# power-v12.net
KiCad netlist of a schematic drawn in Altium Designer
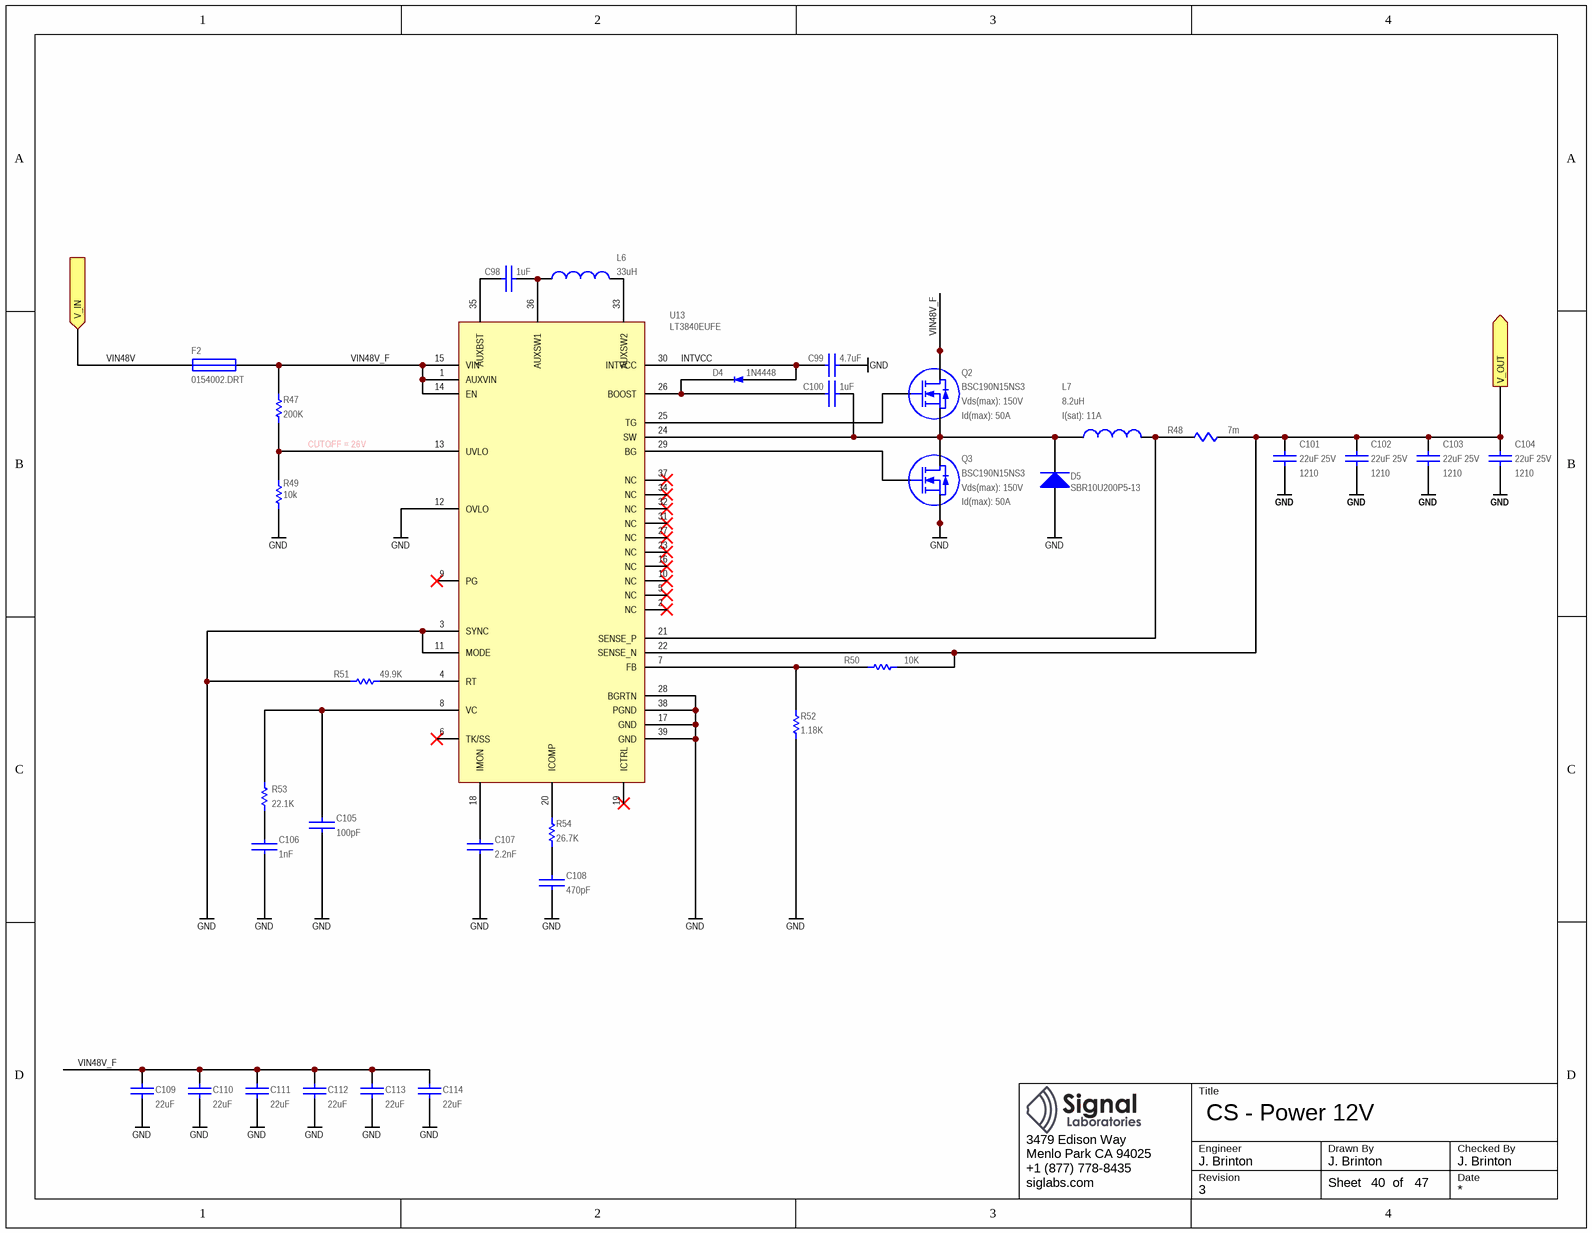
[diagram p0: power-v12.SchDoc]

(export (version "E")
  (design (tool "Eeschema 10.0.6"))
  (components
    (comp (ref "C98")
      (value "1uF")
      (footprint "CAPC100X50X55L25N")
      (description "Ceramic Capacitor 1uF ±10% 10V X5R 0402")
      (fields (field (name "MANUFACTURER") "Murata") (field (name "TOLERANCE") "±10%"))
      (libsource (lib "*") (part "CAP"))
    )
    (comp (ref "C99")
      (value "4.7uF")
      (footprint "CAPC160X80X90L20N")
      (description "Ceramic Capacitor 4.7uF ±10% 25V X5R 0603")
      (fields (field (name "VOLTAGE") "25V") (field (name "MANUFACTURER") "Murata"))
      (libsource (lib "generic") (part "CAP 0603"))
    )
    (comp (ref "C100")
      (value "1uF")
      (footprint "CAPC100X50X55L25N")
      (description "Ceramic Capacitor 1uF ±10% 10V X5R 0402")
      (fields (field (name "MANUFACTURER") "Murata") (field (name "TOLERANCE") "±10%"))
      (libsource (lib "*") (part "CAP"))
    )
    (comp (ref "C101")
      (value "22uF")
      (footprint "CAPC320X250X270L50N")
      (description "Ceramic Capacitor 22uF ±10% 25V X7R 1210")
      (fields
        (field (name "MANUFACTURER") "Murata")
        (field (name "TOLERANCE") "±10%")
        (field (name "VOLTAGE") "25V")
        (field (name "PACKAGE") "1210")
      )
      (libsource (lib "generic") (part "CAP"))
    )
    (comp (ref "C102")
      (value "22uF")
      (footprint "CAPC320X250X270L50N")
      (description "Ceramic Capacitor 22uF ±10% 25V X7R 1210")
      (fields
        (field (name "MANUFACTURER") "Murata")
        (field (name "TOLERANCE") "±10%")
        (field (name "VOLTAGE") "25V")
        (field (name "PACKAGE") "1210")
      )
      (libsource (lib "generic") (part "CAP"))
    )
    (comp (ref "C103")
      (value "22uF")
      (footprint "CAPC320X250X270L50N")
      (description "Ceramic Capacitor 22uF ±10% 25V X7R 1210")
      (fields
        (field (name "MANUFACTURER") "Murata")
        (field (name "TOLERANCE") "±10%")
        (field (name "VOLTAGE") "25V")
        (field (name "PACKAGE") "1210")
      )
      (libsource (lib "generic") (part "CAP"))
    )
    (comp (ref "C104")
      (value "22uF")
      (footprint "CAPC320X250X270L50N")
      (description "Ceramic Capacitor 22uF ±10% 25V X7R 1210")
      (fields
        (field (name "MANUFACTURER") "Murata")
        (field (name "TOLERANCE") "±10%")
        (field (name "VOLTAGE") "25V")
        (field (name "PACKAGE") "1210")
      )
      (libsource (lib "generic") (part "CAP"))
    )
    (comp (ref "C105")
      (value "100pF")
      (footprint "CAPC100X50X55L25N")
      (description "Ceramic Capacitor 100pF ±5% 50V NP0 0402")
      (fields (field (name "MANUFACTURER") "Murata") (field (name "VOLTAGE") "50V"))
      (libsource (lib "*") (part "CAP"))
    )
    (comp (ref "C106")
      (value "1nF")
      (footprint "CAPC100X50X55L25N")
      (description "Ceramic Capacitor 1nF ±5% 50V NP0 0402")
      (fields (field (name "MANUFACTURER") "Murata") (field (name "VOLTAGE") "50V"))
      (libsource (lib "*") (part "CAP"))
    )
    (comp (ref "C107")
      (value "2.2nF")
      (footprint "CAPC100X50X55L25N")
      (description "Ceramic Capacitor 2.2nF ±5% 25V NP0 0402")
      (fields (field (name "MANUFACTURER") "Kemet") (field (name "TOLERANCE") "±5%"))
      (libsource (lib "*") (part "CAP"))
    )
    (comp (ref "C108")
      (value "470pF")
      (footprint "CAPC100X50X55L25N")
      (description "Ceramic Capacitor 470pF ±5% 50V X7R 0402")
      (fields (field (name "MANUFACTURER") "Murata") (field (name "VOLTAGE") "50V"))
      (libsource (lib "*") (part "CAP"))
    )
    (comp (ref "C109")
      (value "22uF")
      (footprint "CAPC600X500X500L160N")
      (description "Ceramic Capacitor 22uF ±20% 50V X7S Stacked")
      (fields (field (name "MANUFACTURER") "TDK") (field (name "TOLERANCE") "±20%"))
      (libsource (lib "generic") (part "CAP"))
    )
    (comp (ref "C110")
      (value "22uF")
      (footprint "CAPC600X500X500L160N")
      (description "Ceramic Capacitor 22uF ±20% 50V X7S Stacked")
      (fields (field (name "MANUFACTURER") "TDK") (field (name "TOLERANCE") "±20%"))
      (libsource (lib "generic") (part "CAP"))
    )
    (comp (ref "C111")
      (value "22uF")
      (footprint "CAPC600X500X500L160N")
      (description "Ceramic Capacitor 22uF ±20% 50V X7S Stacked")
      (fields (field (name "MANUFACTURER") "TDK") (field (name "TOLERANCE") "±20%"))
      (libsource (lib "generic") (part "CAP"))
    )
    (comp (ref "C112")
      (value "22uF")
      (footprint "CAPC600X500X500L160N")
      (description "Ceramic Capacitor 22uF ±20% 50V X7S Stacked")
      (fields (field (name "MANUFACTURER") "TDK") (field (name "TOLERANCE") "±20%"))
      (libsource (lib "generic") (part "CAP"))
    )
    (comp (ref "C113")
      (value "22uF")
      (footprint "CAPC600X500X500L160N")
      (description "Ceramic Capacitor 22uF ±20% 50V X7S Stacked")
      (fields (field (name "MANUFACTURER") "TDK") (field (name "TOLERANCE") "±20%"))
      (libsource (lib "generic") (part "CAP"))
    )
    (comp (ref "C114")
      (value "22uF")
      (footprint "CAPC600X500X500L160N")
      (description "Ceramic Capacitor 22uF ±20% 50V X7S Stacked")
      (fields (field (name "MANUFACTURER") "TDK") (field (name "TOLERANCE") "±20%"))
      (libsource (lib "generic") (part "CAP"))
    )
    (comp (ref "D4")
      (value "1N4448HWS-7-F")
      (footprint "diodes_inc:SOD323")
      (description "Schottky Diode 80V 250mA SOD323")
      (fields (field (name "MANUFACTURER") "Diodes, Inc.") (field (name "ALTERNATIVE P/N") "1N4448"))
      (libsource (lib "diodes_inc") (part "1N4448HWS-7-F"))
    )
    (comp (ref "D5")
      (value "SBR10U200P5-13")
      (footprint "DIODES_POWERDI5")
      (description "Schottky Diode 200V 10A SMD")
      (fields (field (name "MANUFACTURER") "Diodes Inc"))
      (libsource (lib "diodes_inc") (part "PDS5100H"))
    )
    (comp (ref "F2")
      (value "0154002.DRT")
      (footprint "littelfuse:154")
      (description "154 OMNI-BLOK 2A Fuse and Holder")
      (fields (field (name "MANUFACTURER") "Littelfuse"))
      (libsource (lib "Miscellaneous Devices") (part "Fuse 1"))
    )
    (comp (ref "L6")
      (value "33uH")
      (footprint "coilcraft:ME3220")
      (description "Wirewound Power Inductor 33uH ±10% 500mA SMD")
      (fields (field (name "MANUFACTURER") "Coilcraft") (field (name "TOLERANCE") "±10%"))
      (libsource (lib "CamBoard_Pico_70.19K") (part "COIL"))
    )
    (comp (ref "L7")
      (value "8.2uH")
      (footprint "IND-1350")
      (description "Fixed Inductor 8.2uH, 11A(sat), SMD")
      (fields
        (field (name "MANUFACTURER") "Wurth Electronics")
        (field (name "I(SAT)") "11A")
        (field (name "Comment") "7443550820")
      )
      (libsource (lib "CamBoard_Pico_70.19K") (part "COIL"))
    )
    (comp (ref "Q2")
      (value "BSC190N15NS3")
      (footprint "TDSON-8")
      (description "MOSFET N-Channel Enhancement Mode")
      (fields
        (field (name "MANUFACTURER") "Infineon")
        (field (name "VDS(MAX)") "150V")
        (field (name "ID(MAX)") "50A")
      )
      (libsource (lib "infinion") (part "BSC190N15NS3"))
    )
    (comp (ref "Q3")
      (value "BSC190N15NS3")
      (footprint "TDSON-8")
      (description "MOSFET N-Channel Enhancement Mode")
      (fields
        (field (name "MANUFACTURER") "Infineon")
        (field (name "VDS(MAX)") "150V")
        (field (name "ID(MAX)") "50A")
      )
      (libsource (lib "infinion") (part "BSC190N15NS3"))
    )
    (comp (ref "R47")
      (value "200K")
      (footprint "generic:RESC1005X40N")
      (description "Thick Film Resistor 200k ±1% 0402")
      (fields (field (name "MANUFACTURER") "Panasonic") (field (name "TOLERANCE") "±1%"))
      (libsource (lib "Graviton") (part "RES 0402"))
    )
    (comp (ref "R48")
      (value "7m")
      (footprint "RESC3216X80L110N")
      (description "Current Sense Resistor 7mOhm +/-1% SMD 1206")
      (fields (field (name "MANUFACTURER") "Riedon") (field (name "Comment") "CSR1206-0R007F1"))
      (libsource (lib "Kron Library Rev 3") (part "CSR1206-0R001F1"))
    )
    (comp (ref "R49")
      (value "10k")
      (footprint "RESC1005X40N")
      (description "Thick Film Resistor 10k ±1% 0.1W 50V 0402")
      (fields (field (name "MANUFACTURER") "Panasonic") (field (name "TOLERANCE") "±1%"))
      (libsource (lib "generic") (part "RES"))
    )
    (comp (ref "R50")
      (value "10K")
      (footprint "generic:RESC1005X40N")
      (description "Thick Film Resistor 10k ±1% 0.1W 50V 0402")
      (fields (field (name "MANUFACTURER") "Panasonic") (field (name "TOLERANCE") "±1%"))
      (libsource (lib "Graviton") (part "RES 0402"))
    )
    (comp (ref "R51")
      (value "49.9K")
      (footprint "generic:RESC1005X40N")
      (description "Thick Film 49.9k ±1% 0402")
      (fields (field (name "MANUFACTURER") "Panasonic") (field (name "TOLERANCE") "±1%"))
      (libsource (lib "Graviton") (part "RES 0402"))
    )
    (comp (ref "R52")
      (value "1.18K")
      (footprint "generic:RESC1005X40N")
      (description "Thick Film Resistor 1.18k ±1% 0402")
      (fields (field (name "MANUFACTURER") "Yageo") (field (name "TOLERANCE") "±1%"))
      (libsource (lib "Graviton") (part "RES 0402"))
    )
    (comp (ref "R53")
      (value "22.1K")
      (footprint "generic:RESC1005X40N")
      (description "Thick Film Resistor 22.1k ±1% 0402")
      (fields (field (name "MANUFACTURER") "Panasonic") (field (name "TOLERANCE") "±1%"))
      (libsource (lib "Graviton") (part "RES 0402"))
    )
    (comp (ref "R54")
      (value "26.7K")
      (footprint "generic:RESC1005X40N")
      (description "Thick Film Resistor 26.7k ±1% 0402")
      (fields (field (name "MANUFACTURER") "Panasonic") (field (name "TOLERANCE") "±1%"))
      (libsource (lib "Graviton") (part "RES 0402"))
    )
    (comp (ref "U13")
      (value "LT3840EUFE")
      (footprint "linear:QFN39P40_600X400X80L40X20T465X265N")
      (description "Synchronous Regulator Controller")
      (fields (field (name "MANUFACTURER") "Linear Technologies"))
      (libsource (lib "linear") (part "LT3840EUFE"))
    )
  )
  (nets
    (net (code "1") (name "/INTVCC") (class "Default")
      (node (ref "C99") (pin "1") (pinfunction "1_1") (pintype "passive"))
      (node (ref "D4") (pin "A") (pinfunction "A_A") (pintype "passive"))
      (node (ref "U13") (pin "30") (pinfunction "INTVCC_30") (pintype "passive"))
    )
    (net (code "2") (name "/VIN48V") (class "Default")
      (node (ref "F2") (pin "1") (pinfunction "1_1") (pintype "passive"))
    )
    (net (code "3") (name "/VIN48V_F") (class "Default")
      (node (ref "C109") (pin "2") (pinfunction "2_2") (pintype "passive"))
      (node (ref "C110") (pin "2") (pinfunction "2_2") (pintype "passive"))
      (node (ref "C111") (pin "2") (pinfunction "2_2") (pintype "passive"))
      (node (ref "C112") (pin "2") (pinfunction "2_2") (pintype "passive"))
      (node (ref "C113") (pin "2") (pinfunction "2_2") (pintype "passive"))
      (node (ref "C114") (pin "2") (pinfunction "2_2") (pintype "passive"))
      (node (ref "F2") (pin "2") (pinfunction "2_2") (pintype "passive"))
      (node (ref "Q2") (pin "5") (pinfunction "D_5") (pintype "passive"))
      (node (ref "Q2") (pin "6") (pinfunction "D_6") (pintype "passive"))
      (node (ref "Q2") (pin "7") (pinfunction "D_7") (pintype "passive"))
      (node (ref "Q2") (pin "8") (pinfunction "D_8") (pintype "passive"))
      (node (ref "Q2") (pin "9") (pinfunction "D_9") (pintype "passive"))
      (node (ref "R47") (pin "2") (pinfunction "2_2") (pintype "passive"))
      (node (ref "U13") (pin "1") (pinfunction "AUXVIN_1") (pintype "passive"))
      (node (ref "U13") (pin "14") (pinfunction "EN_14") (pintype "passive"))
      (node (ref "U13") (pin "15") (pinfunction "VIN_15") (pintype "passive"))
    )
    (net (code "4") (name "/V_OUT") (class "Default")
      (node (ref "C101") (pin "2") (pinfunction "2_2") (pintype "passive"))
      (node (ref "C102") (pin "2") (pinfunction "2_2") (pintype "passive"))
      (node (ref "C103") (pin "2") (pinfunction "2_2") (pintype "passive"))
      (node (ref "C104") (pin "2") (pinfunction "2_2") (pintype "passive"))
      (node (ref "R48") (pin "2") (pintype "passive"))
      (node (ref "R50") (pin "2") (pinfunction "2_2") (pintype "passive"))
      (node (ref "U13") (pin "22") (pinfunction "SENSE_N_22") (pintype "passive"))
    )
    (net (code "5") (name "GND") (class "Default")
      (node (ref "C101") (pin "1") (pinfunction "1_1") (pintype "passive"))
      (node (ref "C102") (pin "1") (pinfunction "1_1") (pintype "passive"))
      (node (ref "C103") (pin "1") (pinfunction "1_1") (pintype "passive"))
      (node (ref "C104") (pin "1") (pinfunction "1_1") (pintype "passive"))
      (node (ref "C105") (pin "1") (pinfunction "1_1") (pintype "passive"))
      (node (ref "C106") (pin "2") (pinfunction "2_2") (pintype "passive"))
      (node (ref "C107") (pin "2") (pinfunction "2_2") (pintype "passive"))
      (node (ref "C108") (pin "1") (pinfunction "1_1") (pintype "passive"))
      (node (ref "C109") (pin "1") (pinfunction "1_1") (pintype "passive"))
      (node (ref "C110") (pin "1") (pinfunction "1_1") (pintype "passive"))
      (node (ref "C111") (pin "1") (pinfunction "1_1") (pintype "passive"))
      (node (ref "C112") (pin "1") (pinfunction "1_1") (pintype "passive"))
      (node (ref "C113") (pin "1") (pinfunction "1_1") (pintype "passive"))
      (node (ref "C114") (pin "1") (pinfunction "1_1") (pintype "passive"))
      (node (ref "C99") (pin "2") (pinfunction "2_2") (pintype "passive"))
      (node (ref "D5") (pin "A") (pinfunction "A_A") (pintype "power_in"))
      (node (ref "Q3") (pin "1") (pinfunction "S_1") (pintype "passive"))
      (node (ref "Q3") (pin "2") (pinfunction "S_2") (pintype "passive"))
      (node (ref "Q3") (pin "3") (pinfunction "S_3") (pintype "passive"))
      (node (ref "R49") (pin "1") (pinfunction "1_1") (pintype "passive"))
      (node (ref "R51") (pin "2") (pinfunction "2_2") (pintype "passive"))
      (node (ref "R52") (pin "2") (pinfunction "2_2") (pintype "passive"))
      (node (ref "U13") (pin "11") (pinfunction "MODE_11") (pintype "passive"))
      (node (ref "U13") (pin "12") (pinfunction "OVLO_12") (pintype "passive"))
      (node (ref "U13") (pin "17") (pinfunction "GND_17") (pintype "passive"))
      (node (ref "U13") (pin "28") (pinfunction "BGRTN_28") (pintype "passive"))
      (node (ref "U13") (pin "3") (pinfunction "SYNC_3") (pintype "passive"))
      (node (ref "U13") (pin "38") (pinfunction "PGND_38") (pintype "passive"))
      (node (ref "U13") (pin "39") (pinfunction "GND_39") (pintype "passive"))
    )
    (net (code "6") (name "Net-(C106-Pad1)") (class "Default")
      (node (ref "C106") (pin "1") (pinfunction "1_1") (pintype "passive"))
      (node (ref "R53") (pin "1") (pinfunction "1_1") (pintype "passive"))
    )
    (net (code "7") (name "Net-(C108-Pad2)") (class "Default")
      (node (ref "C108") (pin "2") (pinfunction "2_2") (pintype "passive"))
      (node (ref "R54") (pin "2") (pinfunction "2_2") (pintype "passive"))
    )
    (net (code "8") (name "Net-(Q2-G)") (class "Default")
      (node (ref "Q2") (pin "4") (pinfunction "G_4") (pintype "passive"))
      (node (ref "U13") (pin "25") (pinfunction "TG_25") (pintype "passive"))
    )
    (net (code "9") (name "Net-(Q3-G)") (class "Default")
      (node (ref "Q3") (pin "4") (pinfunction "G_4") (pintype "passive"))
      (node (ref "U13") (pin "29") (pinfunction "BG_29") (pintype "passive"))
    )
    (net (code "10") (name "Net-(U13-AUXBST)") (class "Default")
      (node (ref "C98") (pin "2") (pinfunction "2_2") (pintype "passive"))
      (node (ref "U13") (pin "35") (pinfunction "AUXBST_35") (pintype "passive"))
    )
    (net (code "11") (name "Net-(U13-AUXSW1)") (class "Default")
      (node (ref "C98") (pin "1") (pinfunction "1_1") (pintype "passive"))
      (node (ref "L6") (pin "1") (pinfunction "1_1") (pintype "passive"))
      (node (ref "U13") (pin "36") (pinfunction "AUXSW1_36") (pintype "passive"))
    )
    (net (code "12") (name "Net-(U13-AUXSW2)") (class "Default")
      (node (ref "L6") (pin "2") (pinfunction "2_2") (pintype "passive"))
      (node (ref "U13") (pin "33") (pinfunction "AUXSW2_33") (pintype "passive"))
    )
    (net (code "13") (name "Net-(U13-BOOST)") (class "Default")
      (node (ref "C100") (pin "2") (pinfunction "2_2") (pintype "passive"))
      (node (ref "D4") (pin "K") (pinfunction "K_K") (pintype "passive"))
      (node (ref "U13") (pin "26") (pinfunction "BOOST_26") (pintype "passive"))
    )
    (net (code "14") (name "Net-(U13-FB)") (class "Default")
      (node (ref "R50") (pin "1") (pinfunction "1_1") (pintype "passive"))
      (node (ref "R52") (pin "1") (pinfunction "1_1") (pintype "passive"))
      (node (ref "U13") (pin "7") (pinfunction "FB_7") (pintype "passive"))
    )
    (net (code "15") (name "Net-(U13-ICOMP)") (class "Default")
      (node (ref "R54") (pin "1") (pinfunction "1_1") (pintype "passive"))
      (node (ref "U13") (pin "20") (pinfunction "ICOMP_20") (pintype "passive"))
    )
    (net (code "16") (name "Net-(U13-IMON)") (class "Default")
      (node (ref "C107") (pin "1") (pinfunction "1_1") (pintype "passive"))
      (node (ref "U13") (pin "18") (pinfunction "IMON_18") (pintype "passive"))
    )
    (net (code "17") (name "Net-(U13-RT)") (class "Default")
      (node (ref "R51") (pin "1") (pinfunction "1_1") (pintype "passive"))
      (node (ref "U13") (pin "4") (pinfunction "RT_4") (pintype "passive"))
    )
    (net (code "18") (name "Net-(U13-SENSE_P)") (class "Default")
      (node (ref "L7") (pin "2") (pinfunction "2_2") (pintype "passive"))
      (node (ref "R48") (pin "1") (pintype "passive"))
      (node (ref "U13") (pin "21") (pinfunction "SENSE_P_21") (pintype "passive"))
    )
    (net (code "19") (name "Net-(U13-SW)") (class "Default")
      (node (ref "C100") (pin "1") (pinfunction "1_1") (pintype "passive"))
      (node (ref "D5") (pin "K") (pinfunction "K_K") (pintype "passive"))
      (node (ref "L7") (pin "1") (pinfunction "1_1") (pintype "passive"))
      (node (ref "Q2") (pin "1") (pinfunction "S_1") (pintype "passive"))
      (node (ref "Q2") (pin "2") (pinfunction "S_2") (pintype "passive"))
      (node (ref "Q2") (pin "3") (pinfunction "S_3") (pintype "passive"))
      (node (ref "Q3") (pin "5") (pinfunction "D_5") (pintype "passive"))
      (node (ref "Q3") (pin "6") (pinfunction "D_6") (pintype "passive"))
      (node (ref "Q3") (pin "7") (pinfunction "D_7") (pintype "passive"))
      (node (ref "Q3") (pin "8") (pinfunction "D_8") (pintype "passive"))
      (node (ref "Q3") (pin "9") (pinfunction "D_9") (pintype "passive"))
      (node (ref "U13") (pin "24") (pinfunction "SW_24") (pintype "passive"))
    )
    (net (code "20") (name "Net-(U13-UVLO)") (class "Default")
      (node (ref "R47") (pin "1") (pinfunction "1_1") (pintype "passive"))
      (node (ref "R49") (pin "2") (pinfunction "2_2") (pintype "passive"))
      (node (ref "U13") (pin "13") (pinfunction "UVLO_13") (pintype "passive"))
    )
    (net (code "21") (name "Net-(U13-VC)") (class "Default")
      (node (ref "C105") (pin "2") (pinfunction "2_2") (pintype "passive"))
      (node (ref "R53") (pin "2") (pinfunction "2_2") (pintype "passive"))
      (node (ref "U13") (pin "8") (pinfunction "VC_8") (pintype "passive"))
    )
    (net (code "22") (name "unconnected-(U13-ICTRL-Pad19)") (class "Default")
      (node (ref "U13") (pin "19") (pinfunction "ICTRL_19") (pintype "passive+no_connect"))
    )
    (net (code "23") (name "unconnected-(U13-NC-Pad2)") (class "Default")
      (node (ref "U13") (pin "2") (pinfunction "NC_2") (pintype "passive+no_connect"))
    )
    (net (code "24") (name "unconnected-(U13-NC-Pad5)") (class "Default")
      (node (ref "U13") (pin "5") (pinfunction "NC_5") (pintype "passive+no_connect"))
    )
    (net (code "25") (name "unconnected-(U13-NC-Pad10)") (class "Default")
      (node (ref "U13") (pin "10") (pinfunction "NC_10") (pintype "passive+no_connect"))
    )
    (net (code "26") (name "unconnected-(U13-NC-Pad16)") (class "Default")
      (node (ref "U13") (pin "16") (pinfunction "NC_16") (pintype "passive+no_connect"))
    )
    (net (code "27") (name "unconnected-(U13-NC-Pad23)") (class "Default")
      (node (ref "U13") (pin "23") (pinfunction "NC_23") (pintype "passive+no_connect"))
    )
    (net (code "28") (name "unconnected-(U13-NC-Pad27)") (class "Default")
      (node (ref "U13") (pin "27") (pinfunction "NC_27") (pintype "passive+no_connect"))
    )
    (net (code "29") (name "unconnected-(U13-NC-Pad31)") (class "Default")
      (node (ref "U13") (pin "31") (pinfunction "NC_31") (pintype "passive+no_connect"))
    )
    (net (code "30") (name "unconnected-(U13-NC-Pad32)") (class "Default")
      (node (ref "U13") (pin "32") (pinfunction "NC_32") (pintype "passive+no_connect"))
    )
    (net (code "31") (name "unconnected-(U13-NC-Pad34)") (class "Default")
      (node (ref "U13") (pin "34") (pinfunction "NC_34") (pintype "passive+no_connect"))
    )
    (net (code "32") (name "unconnected-(U13-NC-Pad37)") (class "Default")
      (node (ref "U13") (pin "37") (pinfunction "NC_37") (pintype "passive+no_connect"))
    )
    (net (code "33") (name "unconnected-(U13-PG-Pad9)") (class "Default")
      (node (ref "U13") (pin "9") (pinfunction "PG_9") (pintype "passive+no_connect"))
    )
    (net (code "34") (name "unconnected-(U13-TK{slash}SS-Pad6)") (class "Default")
      (node (ref "U13") (pin "6") (pinfunction "TK/SS_6") (pintype "passive+no_connect"))
    )
  )
)
